# CC-S04-V00-SerialComs.net
KiCad netlist of a schematic drawn in Altium Designer
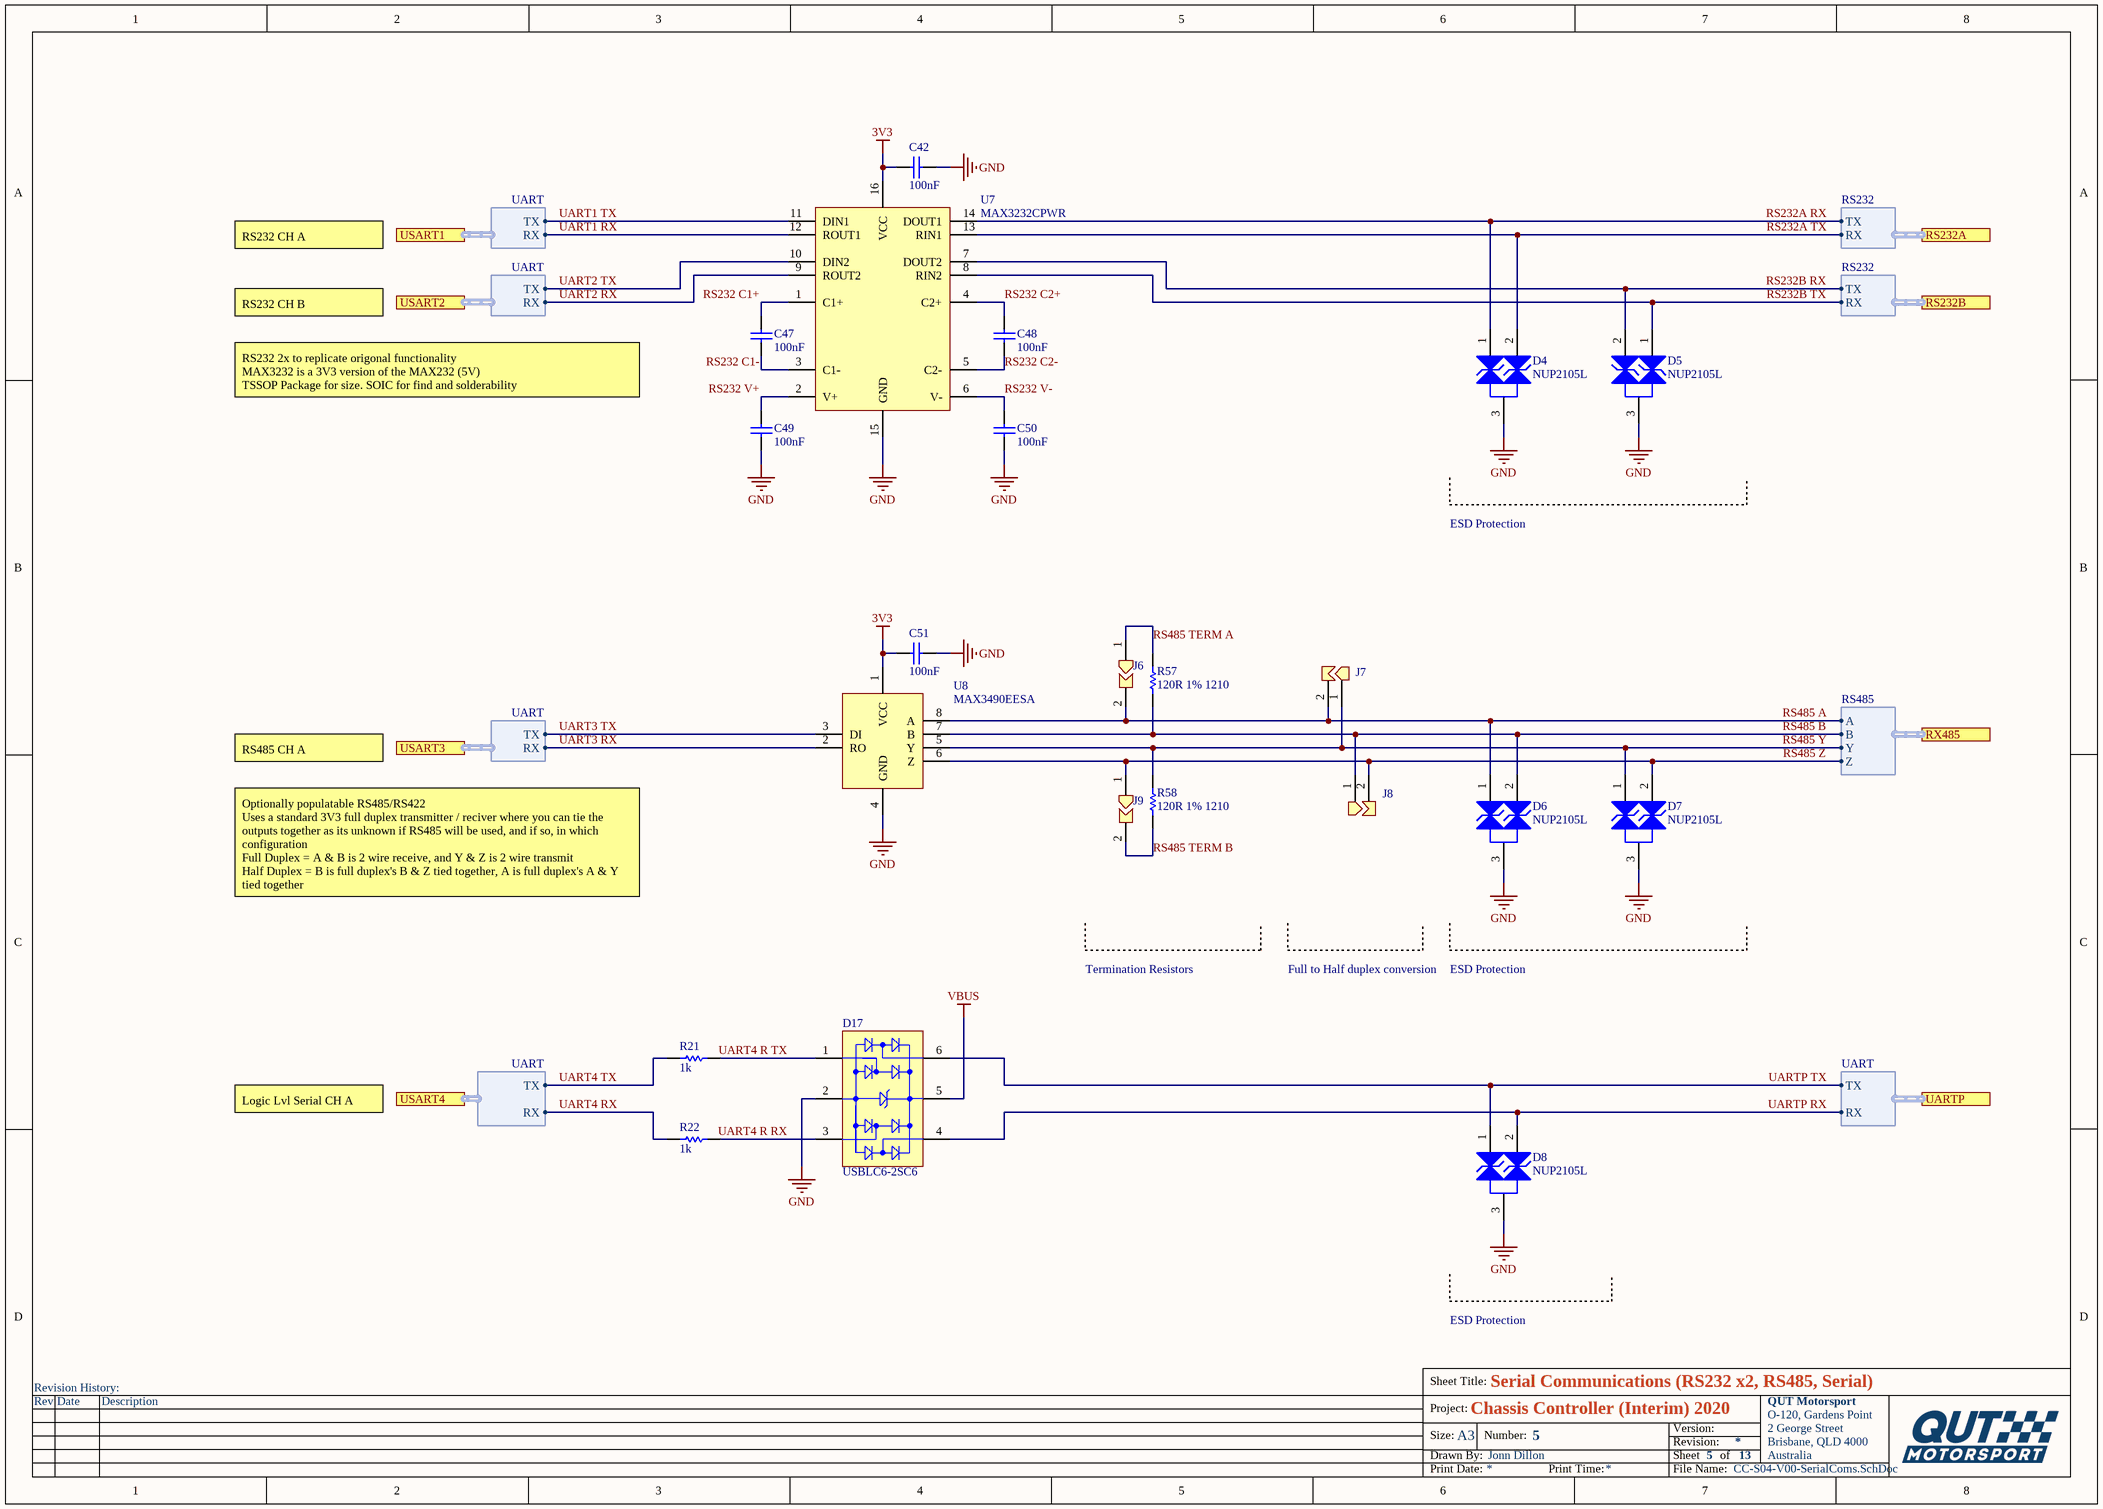
[diagram p0: CC-S04-V00-SerialComs.SchDoc]

(export (version "E")
  (design (tool "Eeschema 10.0.6"))
  (components
    (comp (ref "C42")
      (value "100nF")
      (footprint "Cap_Ceramic_0603")
      (description "Capacitor, Ceramic, SMD, 100nF, 50V, 5%, X7R, 0603")
      (libsource (lib "StandardCapacitors") (part "100nF 50V 5% X7R 0603"))
    )
    (comp (ref "C47")
      (value "100nF")
      (footprint "Cap_Ceramic_0603")
      (description "Capacitor, Ceramic, SMD, 100nF, 50V, 5%, X7R, 0603")
      (libsource (lib "StandardCapacitors") (part "100nF 50V 5% X7R 0603"))
    )
    (comp (ref "C48")
      (value "100nF")
      (footprint "Cap_Ceramic_0603")
      (description "Capacitor, Ceramic, SMD, 100nF, 50V, 5%, X7R, 0603")
      (libsource (lib "StandardCapacitors") (part "100nF 50V 5% X7R 0603"))
    )
    (comp (ref "C49")
      (value "100nF")
      (footprint "Cap_Ceramic_0603")
      (description "Capacitor, Ceramic, SMD, 100nF, 50V, 5%, X7R, 0603")
      (libsource (lib "StandardCapacitors") (part "100nF 50V 5% X7R 0603"))
    )
    (comp (ref "C50")
      (value "100nF")
      (footprint "Cap_Ceramic_0603")
      (description "Capacitor, Ceramic, SMD, 100nF, 50V, 5%, X7R, 0603")
      (libsource (lib "StandardCapacitors") (part "100nF 50V 5% X7R 0603"))
    )
    (comp (ref "C51")
      (value "100nF")
      (footprint "Cap_Ceramic_0603")
      (description "Capacitor, Ceramic, SMD, 100nF, 50V, 5%, X7R, 0603")
      (libsource (lib "StandardCapacitors") (part "100nF 50V 5% X7R 0603"))
    )
    (comp (ref "D4")
      (value "NUP2105L")
      (footprint "NUP2105L")
      (libsource (lib "QUTMS_CANLibrary") (part "NUP2105L"))
    )
    (comp (ref "D5")
      (value "NUP2105L")
      (footprint "NUP2105L")
      (libsource (lib "QUTMS_CANLibrary") (part "NUP2105L"))
    )
    (comp (ref "D6")
      (value "NUP2105L")
      (footprint "NUP2105L")
      (libsource (lib "QUTMS_CANLibrary") (part "NUP2105L"))
    )
    (comp (ref "D7")
      (value "NUP2105L")
      (footprint "NUP2105L")
      (libsource (lib "QUTMS_CANLibrary") (part "NUP2105L"))
    )
    (comp (ref "D8")
      (value "NUP2105L")
      (footprint "NUP2105L")
      (libsource (lib "QUTMS_CANLibrary") (part "NUP2105L"))
    )
    (comp (ref "D17")
      (value "USBLC6-2SC6")
      (footprint "USBLC6-2SC6")
      (description "Very low capacitance ESD protection, 3.5 pF, -40 to 125 degC, 6-Pin SOT23, RoHS, Tape and Reel")
      (libsource (lib "QUTMS_DiodeLibrary") (part "USBLC6-2SC6"))
    )
    (comp (ref "J6")
      (value "Jumper 2Way Solderable")
      (footprint "Jumper_2Way_Solderable")
      (description "Jumper 2Way Vert Solderable")
      (libsource (lib "QUTMS_JumperLibrary") (part "Jumper 2Way Vert Solderable"))
    )
    (comp (ref "J7")
      (value "Jumper 2Way Solderable")
      (footprint "Jumper_2Way_Solderable")
      (description "Jumper 2Way Side Solderable")
      (libsource (lib "QUTMS_JumperLibrary") (part "Jumper 2Way Side Solderable"))
    )
    (comp (ref "J8")
      (value "Jumper 2Way Solderable")
      (footprint "Jumper_2Way_Solderable")
      (description "Jumper 2Way Side Solderable")
      (libsource (lib "QUTMS_JumperLibrary") (part "Jumper 2Way Side Solderable"))
    )
    (comp (ref "J9")
      (value "Jumper 2Way Solderable")
      (footprint "Jumper_2Way_Solderable")
      (description "Jumper 2Way Vert Solderable")
      (libsource (lib "QUTMS_JumperLibrary") (part "Jumper 2Way Vert Solderable"))
    )
    (comp (ref "R21")
      (value "1k")
      (footprint "Res_ThinFilm_0603")
      (description "Resistor, SMD, 1k, 0.1W, 5%, 0603")
      (libsource (lib "StandardResistors") (part "1k 5% 0603"))
    )
    (comp (ref "R22")
      (value "1k")
      (footprint "Res_ThinFilm_0603")
      (description "Resistor, SMD, 1k, 0.1W, 5%, 0603")
      (libsource (lib "StandardResistors") (part "1k 5% 0603"))
    )
    (comp (ref "R57")
      (value "120R 1% 1210")
      (footprint "Res_ThinFilm_1210")
      (description "Resistor, SMD, 120R, 0.25W, 1%, 1210")
      (libsource (lib "StandardResistors") (part "120R 1% 1210"))
    )
    (comp (ref "R58")
      (value "120R 1% 1210")
      (footprint "Res_ThinFilm_1210")
      (description "Resistor, SMD, 120R, 0.25W, 1%, 1210")
      (libsource (lib "StandardResistors") (part "120R 1% 1210"))
    )
    (comp (ref "U7")
      (value "MAX3232CPWR")
      (footprint "MAX3232CPWR")
      (description "MAX3232CPWR - IC, LINE DRIVER, 3-5.5V, SMD")
      (libsource (lib "QUTMS_InterfaceLibrary") (part "MAX3232CPWR"))
    )
    (comp (ref "U8")
      (value "MAX3490EESA")
      (footprint "MAX3490EESA")
      (description "IC, RS422/RS485 TRANSCEIVER, 3.6V, SOIC8")
      (libsource (lib "QUTMS_InterfaceLibrary") (part "MAX3490EESA"))
    )
  )
  (nets
    (net (code "4") (name "/RS232 C1+") (class "Default")
      (node (ref "C47") (pin "2") (pinfunction "2_2") (pintype "passive"))
      (node (ref "U7") (pin "1") (pinfunction "C1+_1") (pintype "passive"))
    )
    (net (code "5") (name "/RS232 C1-") (class "Default")
      (node (ref "C47") (pin "1") (pinfunction "1_1") (pintype "passive"))
      (node (ref "U7") (pin "3") (pinfunction "C1-_3") (pintype "passive"))
    )
    (net (code "6") (name "/RS232 C2+") (class "Default")
      (node (ref "C48") (pin "2") (pinfunction "2_2") (pintype "passive"))
      (node (ref "U7") (pin "4") (pinfunction "C2+_4") (pintype "passive"))
    )
    (net (code "7") (name "/RS232 C2-") (class "Default")
      (node (ref "C48") (pin "1") (pinfunction "1_1") (pintype "passive"))
      (node (ref "U7") (pin "5") (pinfunction "C2-_5") (pintype "passive"))
    )
    (net (code "8") (name "/RS232 V+") (class "Default")
      (node (ref "C49") (pin "2") (pinfunction "2_2") (pintype "passive"))
      (node (ref "U7") (pin "2") (pinfunction "V+_2") (pintype "power_in"))
    )
    (net (code "9") (name "/RS232 V-") (class "Default")
      (node (ref "C50") (pin "2") (pinfunction "2_2") (pintype "passive"))
      (node (ref "U7") (pin "6") (pinfunction "V-_6") (pintype "power_in"))
    )
    (net (code "10") (name "/RS232A RX") (class "Default")
      (node (ref "D4") (pin "1") (pinfunction "1_1") (pintype "passive"))
      (node (ref "U7") (pin "14") (pinfunction "DOUT1_14") (pintype "passive"))
    )
    (net (code "11") (name "/RS232A TX") (class "Default")
      (node (ref "D4") (pin "2") (pinfunction "2_2") (pintype "passive"))
      (node (ref "U7") (pin "13") (pinfunction "RIN1_13") (pintype "passive"))
    )
    (net (code "12") (name "/RS232B RX") (class "Default")
      (node (ref "D5") (pin "2") (pinfunction "2_2") (pintype "passive"))
      (node (ref "U7") (pin "7") (pinfunction "DOUT2_7") (pintype "passive"))
    )
    (net (code "13") (name "/RS232B TX") (class "Default")
      (node (ref "D5") (pin "1") (pinfunction "1_1") (pintype "passive"))
      (node (ref "U7") (pin "8") (pinfunction "RIN2_8") (pintype "passive"))
    )
    (net (code "14") (name "/RS485 A") (class "Default")
      (node (ref "D6") (pin "1") (pinfunction "1_1") (pintype "passive"))
      (node (ref "J6") (pin "2") (pinfunction "2_2") (pintype "passive"))
      (node (ref "J7") (pin "2") (pinfunction "2_2") (pintype "passive"))
      (node (ref "U8") (pin "8") (pinfunction "A_8") (pintype "passive"))
    )
    (net (code "15") (name "/RS485 B") (class "Default")
      (node (ref "D6") (pin "2") (pinfunction "2_2") (pintype "passive"))
      (node (ref "J8") (pin "1") (pinfunction "1_1") (pintype "passive"))
      (node (ref "R57") (pin "1") (pinfunction "1_1") (pintype "passive"))
      (node (ref "U8") (pin "7") (pinfunction "B_7") (pintype "passive"))
    )
    (net (code "16") (name "/RS485 TERM A") (class "Default")
      (node (ref "J6") (pin "1") (pinfunction "1_1") (pintype "passive"))
      (node (ref "R57") (pin "2") (pinfunction "2_2") (pintype "passive"))
    )
    (net (code "17") (name "/RS485 TERM B") (class "Default")
      (node (ref "J9") (pin "2") (pinfunction "2_2") (pintype "passive"))
      (node (ref "R58") (pin "1") (pinfunction "1_1") (pintype "passive"))
    )
    (net (code "18") (name "/RS485 Y") (class "Default")
      (node (ref "D7") (pin "1") (pinfunction "1_1") (pintype "passive"))
      (node (ref "J7") (pin "1") (pinfunction "1_1") (pintype "passive"))
      (node (ref "R58") (pin "2") (pinfunction "2_2") (pintype "passive"))
      (node (ref "U8") (pin "5") (pinfunction "Y_5") (pintype "passive"))
    )
    (net (code "19") (name "/RS485 Z") (class "Default")
      (node (ref "D7") (pin "2") (pinfunction "2_2") (pintype "passive"))
      (node (ref "J8") (pin "2") (pinfunction "2_2") (pintype "passive"))
      (node (ref "J9") (pin "1") (pinfunction "1_1") (pintype "passive"))
      (node (ref "U8") (pin "6") (pinfunction "Z_6") (pintype "passive"))
    )
    (net (code "20") (name "/UART1 RX") (class "Default")
      (node (ref "U7") (pin "12") (pinfunction "ROUT1_12") (pintype "passive"))
    )
    (net (code "21") (name "/UART1 TX") (class "Default")
      (node (ref "U7") (pin "11") (pinfunction "DIN1_11") (pintype "passive"))
    )
    (net (code "22") (name "/UART2 RX") (class "Default")
      (node (ref "U7") (pin "9") (pinfunction "ROUT2_9") (pintype "passive"))
    )
    (net (code "23") (name "/UART2 TX") (class "Default")
      (node (ref "U7") (pin "10") (pinfunction "DIN2_10") (pintype "passive"))
    )
    (net (code "24") (name "/UART3 RX") (class "Default")
      (node (ref "U8") (pin "2") (pinfunction "RO_2") (pintype "passive"))
    )
    (net (code "25") (name "/UART3 TX") (class "Default")
      (node (ref "U8") (pin "3") (pinfunction "DI_3") (pintype "passive"))
    )
    (net (code "26") (name "/UART4 R RX") (class "Default")
      (node (ref "D17") (pin "3") (pinfunction "I/O_2_3") (pintype "passive"))
      (node (ref "R22") (pin "2") (pinfunction "2_2") (pintype "passive"))
    )
    (net (code "27") (name "/UART4 R TX") (class "Default")
      (node (ref "D17") (pin "1") (pinfunction "I/O_1_1") (pintype "passive"))
      (node (ref "R21") (pin "2") (pinfunction "2_2") (pintype "passive"))
    )
    (net (code "28") (name "/UART4 RX") (class "Default")
      (node (ref "R22") (pin "1") (pinfunction "1_1") (pintype "passive"))
    )
    (net (code "29") (name "/UART4 TX") (class "Default")
      (node (ref "R21") (pin "1") (pinfunction "1_1") (pintype "passive"))
    )
    (net (code "30") (name "/UARTP RX") (class "Default")
      (node (ref "D17") (pin "4") (pinfunction "I/O_3_4") (pintype "passive"))
      (node (ref "D8") (pin "2") (pinfunction "2_2") (pintype "passive"))
    )
    (net (code "31") (name "/UARTP TX") (class "Default")
      (node (ref "D17") (pin "6") (pinfunction "I/O_4_6") (pintype "passive"))
      (node (ref "D8") (pin "1") (pinfunction "1_1") (pintype "passive"))
    )
    (net (code "35") (name "3V3") (class "Default")
      (node (ref "C42") (pin "1") (pinfunction "1_1") (pintype "passive"))
      (node (ref "C51") (pin "1") (pinfunction "1_1") (pintype "passive"))
      (node (ref "U7") (pin "16") (pinfunction "VCC_16") (pintype "power_in"))
      (node (ref "U8") (pin "1") (pinfunction "VCC_1") (pintype "passive"))
    )
    (net (code "36") (name "GND") (class "Default")
      (node (ref "C42") (pin "2") (pinfunction "2_2") (pintype "passive"))
      (node (ref "C49") (pin "1") (pinfunction "1_1") (pintype "passive"))
      (node (ref "C50") (pin "1") (pinfunction "1_1") (pintype "passive"))
      (node (ref "C51") (pin "2") (pinfunction "2_2") (pintype "passive"))
      (node (ref "D17") (pin "2") (pinfunction "GND_2") (pintype "passive"))
      (node (ref "D4") (pin "3") (pinfunction "3_3") (pintype "passive"))
      (node (ref "D5") (pin "3") (pinfunction "3_3") (pintype "passive"))
      (node (ref "D6") (pin "3") (pinfunction "3_3") (pintype "passive"))
      (node (ref "D7") (pin "3") (pinfunction "3_3") (pintype "passive"))
      (node (ref "D8") (pin "3") (pinfunction "3_3") (pintype "passive"))
      (node (ref "U7") (pin "15") (pinfunction "GND_15") (pintype "power_in"))
      (node (ref "U8") (pin "4") (pinfunction "GND_4") (pintype "passive"))
    )
    (net (code "37") (name "VBUS") (class "Default")
      (node (ref "D17") (pin "5") (pinfunction "VBUS_5") (pintype "passive"))
    )
  )
)
